# Memory.net
KiCad netlist of a schematic drawn in Altium Designer
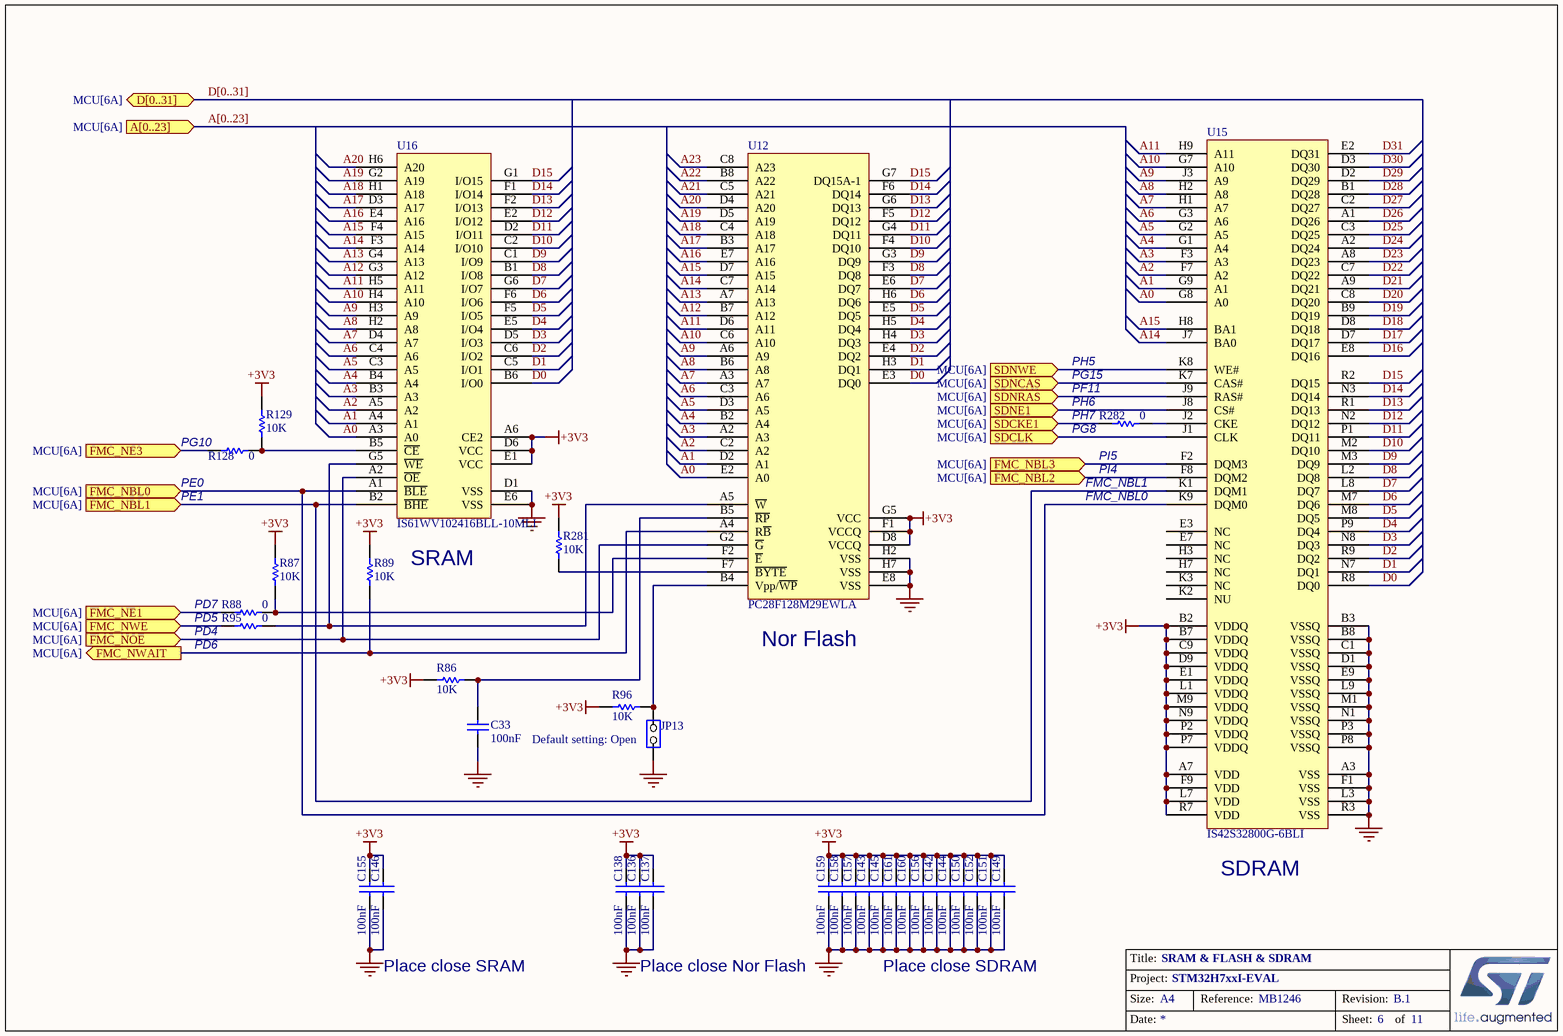
[diagram p0: Memory.SchDoc]

(export (version "E")
  (design (tool "Eeschema 10.0.6"))
  (components
    (comp (ref "C33")
      (value "100nF")
      (footprint "0402_CAP")
      (description "Capacitor")
      (fields (field (name "PUBLISHER") "Altium Limited"))
      (libsource (lib "Miscellaneous Devices") (part "Cap"))
    )
    (comp (ref "C136")
      (value "100nF")
      (footprint "0402_CAP")
      (description "Capacitor")
      (fields (field (name "PUBLISHER") "Altium Limited"))
      (libsource (lib "Miscellaneous Devices") (part "Cap"))
    )
    (comp (ref "C137")
      (value "100nF")
      (footprint "0402_CAP")
      (description "Capacitor")
      (fields (field (name "PUBLISHER") "Altium Limited"))
      (libsource (lib "Miscellaneous Devices") (part "Cap"))
    )
    (comp (ref "C138")
      (value "100nF")
      (footprint "0402_CAP")
      (description "Capacitor")
      (fields (field (name "PUBLISHER") "Altium Limited"))
      (libsource (lib "Miscellaneous Devices") (part "Cap"))
    )
    (comp (ref "C142")
      (value "100nF")
      (footprint "0402_CAP")
      (description "Capacitor")
      (fields (field (name "PUBLISHER") "Altium Limited"))
      (libsource (lib "Miscellaneous Devices") (part "Cap"))
    )
    (comp (ref "C143")
      (value "100nF")
      (footprint "0402_CAP")
      (description "Capacitor")
      (fields (field (name "PUBLISHER") "Altium Limited"))
      (libsource (lib "Miscellaneous Devices") (part "Cap"))
    )
    (comp (ref "C144")
      (value "100nF")
      (footprint "0402_CAP")
      (description "Capacitor")
      (fields (field (name "PUBLISHER") "Altium Limited"))
      (libsource (lib "Miscellaneous Devices") (part "Cap"))
    )
    (comp (ref "C145")
      (value "100nF")
      (footprint "0402_CAP")
      (description "Capacitor")
      (fields (field (name "PUBLISHER") "Altium Limited"))
      (libsource (lib "Miscellaneous Devices") (part "Cap"))
    )
    (comp (ref "C146")
      (value "100nF")
      (footprint "0402_CAP")
      (description "Capacitor")
      (fields (field (name "PUBLISHER") "Altium Limited"))
      (libsource (lib "Miscellaneous Devices") (part "Cap"))
    )
    (comp (ref "C149")
      (value "100nF")
      (footprint "0402_CAP")
      (description "Capacitor")
      (fields (field (name "PUBLISHER") "Altium Limited"))
      (libsource (lib "Miscellaneous Devices") (part "Cap"))
    )
    (comp (ref "C150")
      (value "100nF")
      (footprint "0402_CAP")
      (description "Capacitor")
      (fields (field (name "PUBLISHER") "Altium Limited"))
      (libsource (lib "Miscellaneous Devices") (part "Cap"))
    )
    (comp (ref "C151")
      (value "100nF")
      (footprint "0402_CAP")
      (description "Capacitor")
      (fields (field (name "PUBLISHER") "Altium Limited"))
      (libsource (lib "Miscellaneous Devices") (part "Cap"))
    )
    (comp (ref "C152")
      (value "100nF")
      (footprint "0402_CAP")
      (description "Capacitor")
      (fields (field (name "PUBLISHER") "Altium Limited"))
      (libsource (lib "Miscellaneous Devices") (part "Cap"))
    )
    (comp (ref "C155")
      (value "100nF")
      (footprint "0402_CAP")
      (description "Capacitor")
      (fields (field (name "PUBLISHER") "Altium Limited"))
      (libsource (lib "Miscellaneous Devices") (part "Cap"))
    )
    (comp (ref "C156")
      (value "100nF")
      (footprint "0402_CAP")
      (description "Capacitor")
      (fields (field (name "PUBLISHER") "Altium Limited"))
      (libsource (lib "Miscellaneous Devices") (part "Cap"))
    )
    (comp (ref "C157")
      (value "100nF")
      (footprint "0402_CAP")
      (description "Capacitor")
      (fields (field (name "PUBLISHER") "Altium Limited"))
      (libsource (lib "Miscellaneous Devices") (part "Cap"))
    )
    (comp (ref "C158")
      (value "100nF")
      (footprint "0402_CAP")
      (description "Capacitor")
      (fields (field (name "PUBLISHER") "Altium Limited"))
      (libsource (lib "Miscellaneous Devices") (part "Cap"))
    )
    (comp (ref "C159")
      (value "100nF")
      (footprint "0402_CAP")
      (description "Capacitor")
      (fields (field (name "PUBLISHER") "Altium Limited"))
      (libsource (lib "Miscellaneous Devices") (part "Cap"))
    )
    (comp (ref "C160")
      (value "100nF")
      (footprint "0402_CAP")
      (description "Capacitor")
      (fields (field (name "PUBLISHER") "Altium Limited"))
      (libsource (lib "Miscellaneous Devices") (part "Cap"))
    )
    (comp (ref "C161")
      (value "100nF")
      (footprint "0402_CAP")
      (description "Capacitor")
      (fields (field (name "PUBLISHER") "Altium Limited"))
      (libsource (lib "Miscellaneous Devices") (part "Cap"))
    )
    (comp (ref "JP13") (value "~") (footprint "SIP2") (libsource (lib "*") (part "JP2")))
    (comp (ref "R86")
      (value "10K")
      (footprint "0603R")
      (description "Resistor")
      (fields (field (name "PUBLISHER") "Altium Limited"))
      (libsource (lib "Miscellaneous Devices") (part "Res1"))
    )
    (comp (ref "R87")
      (value "10K")
      (footprint "0603R")
      (description "Resistor")
      (fields (field (name "PUBLISHER") "Altium Limited"))
      (libsource (lib "Miscellaneous Devices") (part "Res1"))
    )
    (comp (ref "R88")
      (value "0")
      (footprint "0603R")
      (description "Resistor")
      (fields (field (name "PUBLISHER") "Altium Limited"))
      (libsource (lib "Miscellaneous Devices") (part "Res1"))
    )
    (comp (ref "R89")
      (value "10K")
      (footprint "0603R")
      (description "Resistor")
      (fields (field (name "PUBLISHER") "Altium Limited"))
      (libsource (lib "Miscellaneous Devices") (part "Res1"))
    )
    (comp (ref "R95")
      (value "0")
      (footprint "0603R")
      (description "Resistor")
      (fields (field (name "PUBLISHER") "Altium Limited"))
      (libsource (lib "Miscellaneous Devices") (part "Res1"))
    )
    (comp (ref "R96")
      (value "10K")
      (footprint "0603R")
      (description "Resistor")
      (fields (field (name "PUBLISHER") "Altium Limited"))
      (libsource (lib "Miscellaneous Devices") (part "Res1"))
    )
    (comp (ref "R128")
      (value "0")
      (footprint "0603R")
      (description "Resistor")
      (fields (field (name "PUBLISHER") "Altium Limited"))
      (libsource (lib "Miscellaneous Devices") (part "Res1"))
    )
    (comp (ref "R129")
      (value "10K")
      (footprint "0603R")
      (description "Resistor")
      (fields (field (name "PUBLISHER") "Altium Limited"))
      (libsource (lib "Miscellaneous Devices") (part "Res1"))
    )
    (comp (ref "R281")
      (value "10K")
      (footprint "0603R")
      (description "Resistor")
      (fields (field (name "PUBLISHER") "Altium Limited"))
      (libsource (lib "Miscellaneous Devices") (part "Res1"))
    )
    (comp (ref "R282")
      (value "0")
      (footprint "0603R")
      (description "Resistor")
      (fields (field (name "PUBLISHER") "Altium Limited"))
      (libsource (lib "Miscellaneous Devices") (part "Res1"))
    )
    (comp (ref "U12")
      (value "PC28F128M29EWLA")
      (footprint "FBGA64_1_11X13")
      (libsource (lib "MB964") (part "M29W128FL70ZA6E"))
    )
    (comp (ref "U15")
      (value "IS42S32800G-6BLI")
      (footprint "FBGA90_0R8_8X13")
      (libsource (lib "mb1045") (part "MT48LC4M32B2B5"))
    )
    (comp (ref "U16")
      (value "IS61WV102416BLL-10MLI")
      (footprint "BGA48_0R75_9X11")
      (libsource (lib "MB901") (part "IS61WV102416BLL-10MLI"))
    )
  )
  (nets
    (net (code "1") (name "+3V3") (class "Default")
      (node (ref "C136") (pin "1") (pinfunction "1_1") (pintype "passive"))
      (node (ref "C137") (pin "1") (pinfunction "1_1") (pintype "passive"))
      (node (ref "C138") (pin "1") (pinfunction "1_1") (pintype "passive"))
      (node (ref "C142") (pin "1") (pinfunction "1_1") (pintype "passive"))
      (node (ref "C143") (pin "1") (pinfunction "1_1") (pintype "passive"))
      (node (ref "C144") (pin "1") (pinfunction "1_1") (pintype "passive"))
      (node (ref "C145") (pin "1") (pinfunction "1_1") (pintype "passive"))
      (node (ref "C146") (pin "1") (pinfunction "1_1") (pintype "passive"))
      (node (ref "C149") (pin "1") (pinfunction "1_1") (pintype "passive"))
      (node (ref "C150") (pin "1") (pinfunction "1_1") (pintype "passive"))
      (node (ref "C151") (pin "1") (pinfunction "1_1") (pintype "passive"))
      (node (ref "C152") (pin "1") (pinfunction "1_1") (pintype "passive"))
      (node (ref "C155") (pin "1") (pinfunction "1_1") (pintype "passive"))
      (node (ref "C156") (pin "1") (pinfunction "1_1") (pintype "passive"))
      (node (ref "C157") (pin "1") (pinfunction "1_1") (pintype "passive"))
      (node (ref "C158") (pin "1") (pinfunction "1_1") (pintype "passive"))
      (node (ref "C159") (pin "1") (pinfunction "1_1") (pintype "passive"))
      (node (ref "C160") (pin "1") (pinfunction "1_1") (pintype "passive"))
      (node (ref "C161") (pin "1") (pinfunction "1_1") (pintype "passive"))
      (node (ref "R129") (pin "2") (pinfunction "2_2") (pintype "passive"))
      (node (ref "R281") (pin "2") (pinfunction "2_2") (pintype "passive"))
      (node (ref "R86") (pin "1") (pinfunction "1_1") (pintype "passive"))
      (node (ref "R87") (pin "2") (pinfunction "2_2") (pintype "passive"))
      (node (ref "R89") (pin "2") (pinfunction "2_2") (pintype "passive"))
      (node (ref "R96") (pin "2") (pinfunction "2_2") (pintype "passive"))
      (node (ref "U12") (pin "D8") (pinfunction "VCCQ_D8") (pintype "passive"))
      (node (ref "U12") (pin "F1") (pinfunction "VCCQ_F1") (pintype "passive"))
      (node (ref "U12") (pin "G5") (pinfunction "VCC_G5") (pintype "passive"))
      (node (ref "U15") (pin "A7") (pinfunction "VDD_A7") (pintype "passive"))
      (node (ref "U15") (pin "B2") (pinfunction "VDDQ_B2") (pintype "passive"))
      (node (ref "U15") (pin "B7") (pinfunction "VDDQ_B7") (pintype "passive"))
      (node (ref "U15") (pin "C9") (pinfunction "VDDQ_C9") (pintype "passive"))
      (node (ref "U15") (pin "D9") (pinfunction "VDDQ_D9") (pintype "passive"))
      (node (ref "U15") (pin "E1") (pinfunction "VDDQ_E1") (pintype "passive"))
      (node (ref "U15") (pin "F9") (pinfunction "VDD_F9") (pintype "passive"))
      (node (ref "U15") (pin "L1") (pinfunction "VDDQ_L1") (pintype "passive"))
      (node (ref "U15") (pin "L7") (pinfunction "VDD_L7") (pintype "passive"))
      (node (ref "U15") (pin "M9") (pinfunction "VDDQ_M9") (pintype "passive"))
      (node (ref "U15") (pin "N9") (pinfunction "VDDQ_N9") (pintype "passive"))
      (node (ref "U15") (pin "P2") (pinfunction "VDDQ_P2") (pintype "passive"))
      (node (ref "U15") (pin "P7") (pinfunction "VDDQ_P7") (pintype "passive"))
      (node (ref "U15") (pin "R7") (pinfunction "VDD_R7") (pintype "passive"))
      (node (ref "U16") (pin "A6") (pinfunction "CE2_A6") (pintype "passive"))
      (node (ref "U16") (pin "D6") (pinfunction "VCC_D6") (pintype "passive"))
      (node (ref "U16") (pin "E1") (pinfunction "VCC_E1") (pintype "passive"))
    )
    (net (code "2") (name "/A0") (class "Default")
      (node (ref "U12") (pin "E2") (pinfunction "A0_E2") (pintype "passive"))
      (node (ref "U15") (pin "G8") (pinfunction "A0_G8") (pintype "passive"))
      (node (ref "U16") (pin "A3") (pinfunction "A0_A3") (pintype "passive"))
    )
    (net (code "3") (name "/A1") (class "Default")
      (node (ref "U12") (pin "D2") (pinfunction "A1_D2") (pintype "passive"))
      (node (ref "U15") (pin "G9") (pinfunction "A1_G9") (pintype "passive"))
      (node (ref "U16") (pin "A4") (pinfunction "A1_A4") (pintype "passive"))
    )
    (net (code "4") (name "/A2") (class "Default")
      (node (ref "U12") (pin "C2") (pinfunction "A2_C2") (pintype "passive"))
      (node (ref "U15") (pin "F7") (pinfunction "A2_F7") (pintype "passive"))
      (node (ref "U16") (pin "A5") (pinfunction "A2_A5") (pintype "passive"))
    )
    (net (code "5") (name "/A3") (class "Default")
      (node (ref "U12") (pin "A2") (pinfunction "A3_A2") (pintype "passive"))
      (node (ref "U15") (pin "F3") (pinfunction "A3_F3") (pintype "passive"))
      (node (ref "U16") (pin "B3") (pinfunction "A3_B3") (pintype "passive"))
    )
    (net (code "6") (name "/A4") (class "Default")
      (node (ref "U12") (pin "B2") (pinfunction "A4_B2") (pintype "passive"))
      (node (ref "U15") (pin "G1") (pinfunction "A4_G1") (pintype "passive"))
      (node (ref "U16") (pin "B4") (pinfunction "A4_B4") (pintype "passive"))
    )
    (net (code "7") (name "/A5") (class "Default")
      (node (ref "U12") (pin "D3") (pinfunction "A5_D3") (pintype "passive"))
      (node (ref "U15") (pin "G2") (pinfunction "A5_G2") (pintype "passive"))
      (node (ref "U16") (pin "C3") (pinfunction "A5_C3") (pintype "passive"))
    )
    (net (code "8") (name "/A6") (class "Default")
      (node (ref "U12") (pin "C3") (pinfunction "A6_C3") (pintype "passive"))
      (node (ref "U15") (pin "G3") (pinfunction "A6_G3") (pintype "passive"))
      (node (ref "U16") (pin "C4") (pinfunction "A6_C4") (pintype "passive"))
    )
    (net (code "9") (name "/A7") (class "Default")
      (node (ref "U12") (pin "A3") (pinfunction "A7_A3") (pintype "passive"))
      (node (ref "U15") (pin "H1") (pinfunction "A7_H1") (pintype "passive"))
      (node (ref "U16") (pin "D4") (pinfunction "A7_D4") (pintype "passive"))
    )
    (net (code "10") (name "/A8") (class "Default")
      (node (ref "U12") (pin "B6") (pinfunction "A8_B6") (pintype "passive"))
      (node (ref "U15") (pin "H2") (pinfunction "A8_H2") (pintype "passive"))
      (node (ref "U16") (pin "H2") (pinfunction "A8_H2") (pintype "passive"))
    )
    (net (code "11") (name "/A9") (class "Default")
      (node (ref "U12") (pin "A6") (pinfunction "A9_A6") (pintype "passive"))
      (node (ref "U15") (pin "J3") (pinfunction "A9_J3") (pintype "passive"))
      (node (ref "U16") (pin "H3") (pinfunction "A9_H3") (pintype "passive"))
    )
    (net (code "12") (name "/A10") (class "Default")
      (node (ref "U12") (pin "C6") (pinfunction "A10_C6") (pintype "passive"))
      (node (ref "U15") (pin "G7") (pinfunction "A10_G7") (pintype "passive"))
      (node (ref "U16") (pin "H4") (pinfunction "A10_H4") (pintype "passive"))
    )
    (net (code "13") (name "/A11") (class "Default")
      (node (ref "U12") (pin "D6") (pinfunction "A11_D6") (pintype "passive"))
      (node (ref "U15") (pin "H9") (pinfunction "A11_H9") (pintype "passive"))
      (node (ref "U16") (pin "H5") (pinfunction "A11_H5") (pintype "passive"))
    )
    (net (code "14") (name "/A12") (class "Default")
      (node (ref "U12") (pin "B7") (pinfunction "A12_B7") (pintype "passive"))
      (node (ref "U16") (pin "G3") (pinfunction "A12_G3") (pintype "passive"))
    )
    (net (code "15") (name "/A13") (class "Default")
      (node (ref "U12") (pin "A7") (pinfunction "A13_A7") (pintype "passive"))
      (node (ref "U16") (pin "G4") (pinfunction "A13_G4") (pintype "passive"))
    )
    (net (code "16") (name "/A14") (class "Default")
      (node (ref "U12") (pin "C7") (pinfunction "A14_C7") (pintype "passive"))
      (node (ref "U15") (pin "J7") (pinfunction "BA0_J7") (pintype "passive"))
      (node (ref "U16") (pin "F3") (pinfunction "A14_F3") (pintype "passive"))
    )
    (net (code "17") (name "/A15") (class "Default")
      (node (ref "U12") (pin "D7") (pinfunction "A15_D7") (pintype "passive"))
      (node (ref "U15") (pin "H8") (pinfunction "BA1_H8") (pintype "passive"))
      (node (ref "U16") (pin "F4") (pinfunction "A15_F4") (pintype "passive"))
    )
    (net (code "18") (name "/A16") (class "Default")
      (node (ref "U12") (pin "E7") (pinfunction "A16_E7") (pintype "passive"))
      (node (ref "U16") (pin "E4") (pinfunction "A16_E4") (pintype "passive"))
    )
    (net (code "19") (name "/A17") (class "Default")
      (node (ref "U12") (pin "B3") (pinfunction "A17_B3") (pintype "passive"))
      (node (ref "U16") (pin "D3") (pinfunction "A17_D3") (pintype "passive"))
    )
    (net (code "20") (name "/A18") (class "Default")
      (node (ref "U12") (pin "C4") (pinfunction "A18_C4") (pintype "passive"))
      (node (ref "U16") (pin "H1") (pinfunction "A18_H1") (pintype "passive"))
    )
    (net (code "21") (name "/A19") (class "Default")
      (node (ref "U12") (pin "D5") (pinfunction "A19_D5") (pintype "passive"))
      (node (ref "U16") (pin "G2") (pinfunction "A19_G2") (pintype "passive"))
    )
    (net (code "22") (name "/A20") (class "Default")
      (node (ref "U12") (pin "D4") (pinfunction "A20_D4") (pintype "passive"))
      (node (ref "U16") (pin "H6") (pinfunction "A20_H6") (pintype "passive"))
    )
    (net (code "23") (name "/A21") (class "Default")
      (node (ref "U12") (pin "C5") (pinfunction "A21_C5") (pintype "passive"))
    )
    (net (code "24") (name "/A22") (class "Default")
      (node (ref "U12") (pin "B8") (pinfunction "A22_B8") (pintype "passive"))
    )
    (net (code "25") (name "/A23") (class "Default")
      (node (ref "U12") (pin "C8") (pinfunction "A23_C8") (pintype "passive"))
    )
    (net (code "27") (name "/D0") (class "Default")
      (node (ref "U12") (pin "E3") (pinfunction "DQ0_E3") (pintype "passive"))
      (node (ref "U15") (pin "R8") (pinfunction "DQ0_R8") (pintype "passive"))
      (node (ref "U16") (pin "B6") (pinfunction "I/O0_B6") (pintype "passive"))
    )
    (net (code "28") (name "/D1") (class "Default")
      (node (ref "U12") (pin "H3") (pinfunction "DQ1_H3") (pintype "passive"))
      (node (ref "U15") (pin "N7") (pinfunction "DQ1_N7") (pintype "passive"))
      (node (ref "U16") (pin "C5") (pinfunction "I/O1_C5") (pintype "passive"))
    )
    (net (code "29") (name "/D2") (class "Default")
      (node (ref "U12") (pin "E4") (pinfunction "DQ2_E4") (pintype "passive"))
      (node (ref "U15") (pin "R9") (pinfunction "DQ2_R9") (pintype "passive"))
      (node (ref "U16") (pin "C6") (pinfunction "I/O2_C6") (pintype "passive"))
    )
    (net (code "30") (name "/D3") (class "Default")
      (node (ref "U12") (pin "H4") (pinfunction "DQ3_H4") (pintype "passive"))
      (node (ref "U15") (pin "N8") (pinfunction "DQ3_N8") (pintype "passive"))
      (node (ref "U16") (pin "D5") (pinfunction "I/O3_D5") (pintype "passive"))
    )
    (net (code "31") (name "/D4") (class "Default")
      (node (ref "U12") (pin "H5") (pinfunction "DQ4_H5") (pintype "passive"))
      (node (ref "U15") (pin "P9") (pinfunction "DQ4_P9") (pintype "passive"))
      (node (ref "U16") (pin "E5") (pinfunction "I/O4_E5") (pintype "passive"))
    )
    (net (code "32") (name "/D5") (class "Default")
      (node (ref "U12") (pin "E5") (pinfunction "DQ5_E5") (pintype "passive"))
      (node (ref "U15") (pin "M8") (pinfunction "DQ5_M8") (pintype "passive"))
      (node (ref "U16") (pin "F5") (pinfunction "I/O5_F5") (pintype "passive"))
    )
    (net (code "33") (name "/D6") (class "Default")
      (node (ref "U12") (pin "H6") (pinfunction "DQ6_H6") (pintype "passive"))
      (node (ref "U15") (pin "M7") (pinfunction "DQ6_M7") (pintype "passive"))
      (node (ref "U16") (pin "F6") (pinfunction "I/O6_F6") (pintype "passive"))
    )
    (net (code "34") (name "/D7") (class "Default")
      (node (ref "U12") (pin "E6") (pinfunction "DQ7_E6") (pintype "passive"))
      (node (ref "U15") (pin "L8") (pinfunction "DQ7_L8") (pintype "passive"))
      (node (ref "U16") (pin "G6") (pinfunction "I/O7_G6") (pintype "passive"))
    )
    (net (code "35") (name "/D8") (class "Default")
      (node (ref "U12") (pin "F3") (pinfunction "DQ8_F3") (pintype "passive"))
      (node (ref "U15") (pin "L2") (pinfunction "DQ8_L2") (pintype "passive"))
      (node (ref "U16") (pin "B1") (pinfunction "I/O8_B1") (pintype "passive"))
    )
    (net (code "36") (name "/D9") (class "Default")
      (node (ref "U12") (pin "G3") (pinfunction "DQ9_G3") (pintype "passive"))
      (node (ref "U15") (pin "M3") (pinfunction "DQ9_M3") (pintype "passive"))
      (node (ref "U16") (pin "C1") (pinfunction "I/O9_C1") (pintype "passive"))
    )
    (net (code "37") (name "/D10") (class "Default")
      (node (ref "U12") (pin "F4") (pinfunction "DQ10_F4") (pintype "passive"))
      (node (ref "U15") (pin "M2") (pinfunction "DQ10_M2") (pintype "passive"))
      (node (ref "U16") (pin "C2") (pinfunction "I/O10_C2") (pintype "passive"))
    )
    (net (code "38") (name "/D11") (class "Default")
      (node (ref "U12") (pin "G4") (pinfunction "DQ11_G4") (pintype "passive"))
      (node (ref "U15") (pin "P1") (pinfunction "DQ11_P1") (pintype "passive"))
      (node (ref "U16") (pin "D2") (pinfunction "I/O11_D2") (pintype "passive"))
    )
    (net (code "39") (name "/D12") (class "Default")
      (node (ref "U12") (pin "F5") (pinfunction "DQ12_F5") (pintype "passive"))
      (node (ref "U15") (pin "N2") (pinfunction "DQ12_N2") (pintype "passive"))
      (node (ref "U16") (pin "E2") (pinfunction "I/O12_E2") (pintype "passive"))
    )
    (net (code "40") (name "/D13") (class "Default")
      (node (ref "U12") (pin "G6") (pinfunction "DQ13_G6") (pintype "passive"))
      (node (ref "U15") (pin "R1") (pinfunction "DQ13_R1") (pintype "passive"))
      (node (ref "U16") (pin "F2") (pinfunction "I/O13_F2") (pintype "passive"))
    )
    (net (code "41") (name "/D14") (class "Default")
      (node (ref "U12") (pin "F6") (pinfunction "DQ14_F6") (pintype "passive"))
      (node (ref "U15") (pin "N3") (pinfunction "DQ14_N3") (pintype "passive"))
      (node (ref "U16") (pin "F1") (pinfunction "I/O14_F1") (pintype "passive"))
    )
    (net (code "42") (name "/D15") (class "Default")
      (node (ref "U12") (pin "G7") (pinfunction "DQ15A-1_G7") (pintype "passive"))
      (node (ref "U15") (pin "R2") (pinfunction "DQ15_R2") (pintype "passive"))
      (node (ref "U16") (pin "G1") (pinfunction "I/O15_G1") (pintype "passive"))
    )
    (net (code "43") (name "/D16") (class "Default")
      (node (ref "U15") (pin "E8") (pinfunction "DQ16_E8") (pintype "passive"))
    )
    (net (code "44") (name "/D17") (class "Default")
      (node (ref "U15") (pin "D7") (pinfunction "DQ17_D7") (pintype "passive"))
    )
    (net (code "45") (name "/D18") (class "Default")
      (node (ref "U15") (pin "D8") (pinfunction "DQ18_D8") (pintype "passive"))
    )
    (net (code "46") (name "/D19") (class "Default")
      (node (ref "U15") (pin "B9") (pinfunction "DQ19_B9") (pintype "passive"))
    )
    (net (code "47") (name "/D20") (class "Default")
      (node (ref "U15") (pin "C8") (pinfunction "DQ20_C8") (pintype "passive"))
    )
    (net (code "48") (name "/D21") (class "Default")
      (node (ref "U15") (pin "A9") (pinfunction "DQ21_A9") (pintype "passive"))
    )
    (net (code "49") (name "/D22") (class "Default")
      (node (ref "U15") (pin "C7") (pinfunction "DQ22_C7") (pintype "passive"))
    )
    (net (code "50") (name "/D23") (class "Default")
      (node (ref "U15") (pin "A8") (pinfunction "DQ23_A8") (pintype "passive"))
    )
    (net (code "51") (name "/D24") (class "Default")
      (node (ref "U15") (pin "A2") (pinfunction "DQ24_A2") (pintype "passive"))
    )
    (net (code "52") (name "/D25") (class "Default")
      (node (ref "U15") (pin "C3") (pinfunction "DQ25_C3") (pintype "passive"))
    )
    (net (code "53") (name "/D26") (class "Default")
      (node (ref "U15") (pin "A1") (pinfunction "DQ26_A1") (pintype "passive"))
    )
    (net (code "54") (name "/D27") (class "Default")
      (node (ref "U15") (pin "C2") (pinfunction "DQ27_C2") (pintype "passive"))
    )
    (net (code "55") (name "/D28") (class "Default")
      (node (ref "U15") (pin "B1") (pinfunction "DQ28_B1") (pintype "passive"))
    )
    (net (code "56") (name "/D29") (class "Default")
      (node (ref "U15") (pin "D2") (pinfunction "DQ29_D2") (pintype "passive"))
    )
    (net (code "57") (name "/D30") (class "Default")
      (node (ref "U15") (pin "D3") (pinfunction "DQ30_D3") (pintype "passive"))
    )
    (net (code "58") (name "/D31") (class "Default")
      (node (ref "U15") (pin "E2") (pinfunction "DQ31_E2") (pintype "passive"))
    )
    (net (code "60") (name "/FMC_NBL0") (class "Default")
      (node (ref "U15") (pin "K9") (pinfunction "DQM0_K9") (pintype "passive"))
      (node (ref "U16") (pin "A1") (pinfunction "~{BLE}_A1") (pintype "passive"))
    )
    (net (code "61") (name "/FMC_NBL1") (class "Default")
      (node (ref "U15") (pin "K1") (pinfunction "DQM1_K1") (pintype "passive"))
      (node (ref "U16") (pin "B2") (pinfunction "~{BHE}_B2") (pintype "passive"))
    )
    (net (code "62") (name "/FMC_NBL2") (class "Default")
      (node (ref "U15") (pin "F8") (pinfunction "DQM2_F8") (pintype "passive"))
    )
    (net (code "63") (name "/FMC_NBL3") (class "Default")
      (node (ref "U15") (pin "F2") (pinfunction "DQM3_F2") (pintype "passive"))
    )
    (net (code "64") (name "/FMC_NE1") (class "Default")
      (node (ref "R88") (pin "2") (pinfunction "2_2") (pintype "passive"))
    )
    (net (code "65") (name "/FMC_NE3") (class "Default")
      (node (ref "R128") (pin "2") (pinfunction "2_2") (pintype "passive"))
    )
    (net (code "66") (name "/FMC_NOE") (class "Default")
      (node (ref "U12") (pin "G2") (pinfunction "~{G}_G2") (pintype "passive"))
      (node (ref "U16") (pin "A2") (pinfunction "~{OE}_A2") (pintype "passive"))
    )
    (net (code "67") (name "/FMC_NWAIT") (class "Default")
      (node (ref "R89") (pin "1") (pinfunction "1_1") (pintype "passive"))
      (node (ref "U12") (pin "A4") (pinfunction "R~{B}_A4") (pintype "passive"))
    )
    (net (code "68") (name "/FMC_NWE") (class "Default")
      (node (ref "R95") (pin "2") (pinfunction "2_2") (pintype "passive"))
    )
    (net (code "69") (name "/SDCKE1") (class "Default")
      (node (ref "R282") (pin "2") (pinfunction "2_2") (pintype "passive"))
    )
    (net (code "70") (name "/SDCLK") (class "Default")
      (node (ref "U15") (pin "J1") (pinfunction "CLK_J1") (pintype "passive"))
    )
    (net (code "71") (name "/SDNCAS") (class "Default")
      (node (ref "U15") (pin "K7") (pinfunction "CAS#_K7") (pintype "passive"))
    )
    (net (code "72") (name "/SDNE1") (class "Default")
      (node (ref "U15") (pin "J8") (pinfunction "CS#_J8") (pintype "passive"))
    )
    (net (code "73") (name "/SDNRAS") (class "Default")
      (node (ref "U15") (pin "J9") (pinfunction "RAS#_J9") (pintype "passive"))
    )
    (net (code "74") (name "/SDNWE") (class "Default")
      (node (ref "U15") (pin "K8") (pinfunction "WE#_K8") (pintype "passive"))
    )
    (net (code "75") (name "GND") (class "Default")
      (node (ref "C136") (pin "2") (pinfunction "2_2") (pintype "passive"))
      (node (ref "C137") (pin "2") (pinfunction "2_2") (pintype "passive"))
      (node (ref "C138") (pin "2") (pinfunction "2_2") (pintype "passive"))
      (node (ref "C142") (pin "2") (pinfunction "2_2") (pintype "passive"))
      (node (ref "C143") (pin "2") (pinfunction "2_2") (pintype "passive"))
      (node (ref "C144") (pin "2") (pinfunction "2_2") (pintype "passive"))
      (node (ref "C145") (pin "2") (pinfunction "2_2") (pintype "passive"))
      (node (ref "C146") (pin "2") (pinfunction "2_2") (pintype "passive"))
      (node (ref "C149") (pin "2") (pinfunction "2_2") (pintype "passive"))
      (node (ref "C150") (pin "2") (pinfunction "2_2") (pintype "passive"))
      (node (ref "C151") (pin "2") (pinfunction "2_2") (pintype "passive"))
      (node (ref "C152") (pin "2") (pinfunction "2_2") (pintype "passive"))
      (node (ref "C155") (pin "2") (pinfunction "2_2") (pintype "passive"))
      (node (ref "C156") (pin "2") (pinfunction "2_2") (pintype "passive"))
      (node (ref "C157") (pin "2") (pinfunction "2_2") (pintype "passive"))
      (node (ref "C158") (pin "2") (pinfunction "2_2") (pintype "passive"))
      (node (ref "C159") (pin "2") (pinfunction "2_2") (pintype "passive"))
      (node (ref "C160") (pin "2") (pinfunction "2_2") (pintype "passive"))
      (node (ref "C161") (pin "2") (pinfunction "2_2") (pintype "passive"))
      (node (ref "C33") (pin "2") (pinfunction "2_2") (pintype "passive"))
      (node (ref "JP13") (pin "1") (pinfunction "COMMON_1") (pintype "passive"))
      (node (ref "U12") (pin "E8") (pinfunction "VSS_E8") (pintype "passive"))
      (node (ref "U12") (pin "H2") (pinfunction "VSS_H2") (pintype "passive"))
      (node (ref "U12") (pin "H7") (pinfunction "VSS_H7") (pintype "passive"))
      (node (ref "U15") (pin "A3") (pinfunction "VSS_A3") (pintype "passive"))
      (node (ref "U15") (pin "B3") (pinfunction "VSSQ_B3") (pintype "passive"))
      (node (ref "U15") (pin "B8") (pinfunction "VSSQ_B8") (pintype "passive"))
      (node (ref "U15") (pin "C1") (pinfunction "VSSQ_C1") (pintype "passive"))
      (node (ref "U15") (pin "D1") (pinfunction "VSSQ_D1") (pintype "passive"))
      (node (ref "U15") (pin "E9") (pinfunction "VSSQ_E9") (pintype "passive"))
      (node (ref "U15") (pin "F1") (pinfunction "VSS_F1") (pintype "passive"))
      (node (ref "U15") (pin "L3") (pinfunction "VSS_L3") (pintype "passive"))
      (node (ref "U15") (pin "L9") (pinfunction "VSSQ_L9") (pintype "passive"))
      (node (ref "U15") (pin "M1") (pinfunction "VSSQ_M1") (pintype "passive"))
      (node (ref "U15") (pin "N1") (pinfunction "VSSQ_N1") (pintype "passive"))
      (node (ref "U15") (pin "P3") (pinfunction "VSSQ_P3") (pintype "passive"))
      (node (ref "U15") (pin "P8") (pinfunction "VSSQ_P8") (pintype "passive"))
      (node (ref "U15") (pin "R3") (pinfunction "VSS_R3") (pintype "passive"))
      (node (ref "U16") (pin "D1") (pinfunction "VSS_D1") (pintype "passive"))
      (node (ref "U16") (pin "E6") (pinfunction "VSS_E6") (pintype "passive"))
    )
    (net (code "76") (name "Net-(JP13-NO)") (class "Default")
      (node (ref "JP13") (pin "2") (pinfunction "NO_2") (pintype "passive"))
      (node (ref "R96") (pin "1") (pinfunction "1_1") (pintype "passive"))
      (node (ref "U12") (pin "B4") (pinfunction "Vpp/~{WP}_B4") (pintype "passive"))
    )
    (net (code "77") (name "Net-(U12-~{BYTE})") (class "Default")
      (node (ref "R281") (pin "1") (pinfunction "1_1") (pintype "passive"))
      (node (ref "U12") (pin "F7") (pinfunction "~{BYTE}_F7") (pintype "passive"))
    )
    (net (code "78") (name "Net-(U12-~{E})") (class "Default")
      (node (ref "R87") (pin "1") (pinfunction "1_1") (pintype "passive"))
      (node (ref "R88") (pin "1") (pinfunction "1_1") (pintype "passive"))
      (node (ref "U12") (pin "F2") (pinfunction "~{E}_F2") (pintype "passive"))
    )
    (net (code "79") (name "Net-(U12-~{RP})") (class "Default")
      (node (ref "C33") (pin "1") (pinfunction "1_1") (pintype "passive"))
      (node (ref "R86") (pin "2") (pinfunction "2_2") (pintype "passive"))
      (node (ref "U12") (pin "B5") (pinfunction "~{RP}_B5") (pintype "passive"))
    )
    (net (code "80") (name "Net-(U12-~{W})") (class "Default")
      (node (ref "R95") (pin "1") (pinfunction "1_1") (pintype "passive"))
      (node (ref "U12") (pin "A5") (pinfunction "~{W}_A5") (pintype "passive"))
      (node (ref "U16") (pin "G5") (pinfunction "~{WE}_G5") (pintype "passive"))
    )
    (net (code "81") (name "Net-(U15-CKE)") (class "Default")
      (node (ref "R282") (pin "1") (pinfunction "1_1") (pintype "passive"))
      (node (ref "U15") (pin "J2") (pinfunction "CKE_J2") (pintype "passive"))
    )
    (net (code "82") (name "Net-(U16-~{CE})") (class "Default")
      (node (ref "R128") (pin "1") (pinfunction "1_1") (pintype "passive"))
      (node (ref "R129") (pin "1") (pinfunction "1_1") (pintype "passive"))
      (node (ref "U16") (pin "B5") (pinfunction "~{CE}_B5") (pintype "passive"))
    )
    (net (code "83") (name "unconnected-(U15-NC-PadE3)") (class "Default")
      (node (ref "U15") (pin "E3") (pinfunction "NC_E3") (pintype "passive"))
    )
    (net (code "84") (name "unconnected-(U15-NC-PadE7)") (class "Default")
      (node (ref "U15") (pin "E7") (pinfunction "NC_E7") (pintype "passive"))
    )
    (net (code "85") (name "unconnected-(U15-NC-PadH3)") (class "Default")
      (node (ref "U15") (pin "H3") (pinfunction "NC_H3") (pintype "passive"))
    )
    (net (code "86") (name "unconnected-(U15-NC-PadH7)") (class "Default")
      (node (ref "U15") (pin "H7") (pinfunction "NC_H7") (pintype "passive"))
    )
    (net (code "87") (name "unconnected-(U15-NC-PadK3)") (class "Default")
      (node (ref "U15") (pin "K3") (pinfunction "NC_K3") (pintype "passive"))
    )
    (net (code "88") (name "unconnected-(U15-NU-PadK2)") (class "Default")
      (node (ref "U15") (pin "K2") (pinfunction "NU_K2") (pintype "passive"))
    )
  )
)
